# schematics.net
KiCad netlist of a schematic drawn in Altium Designer
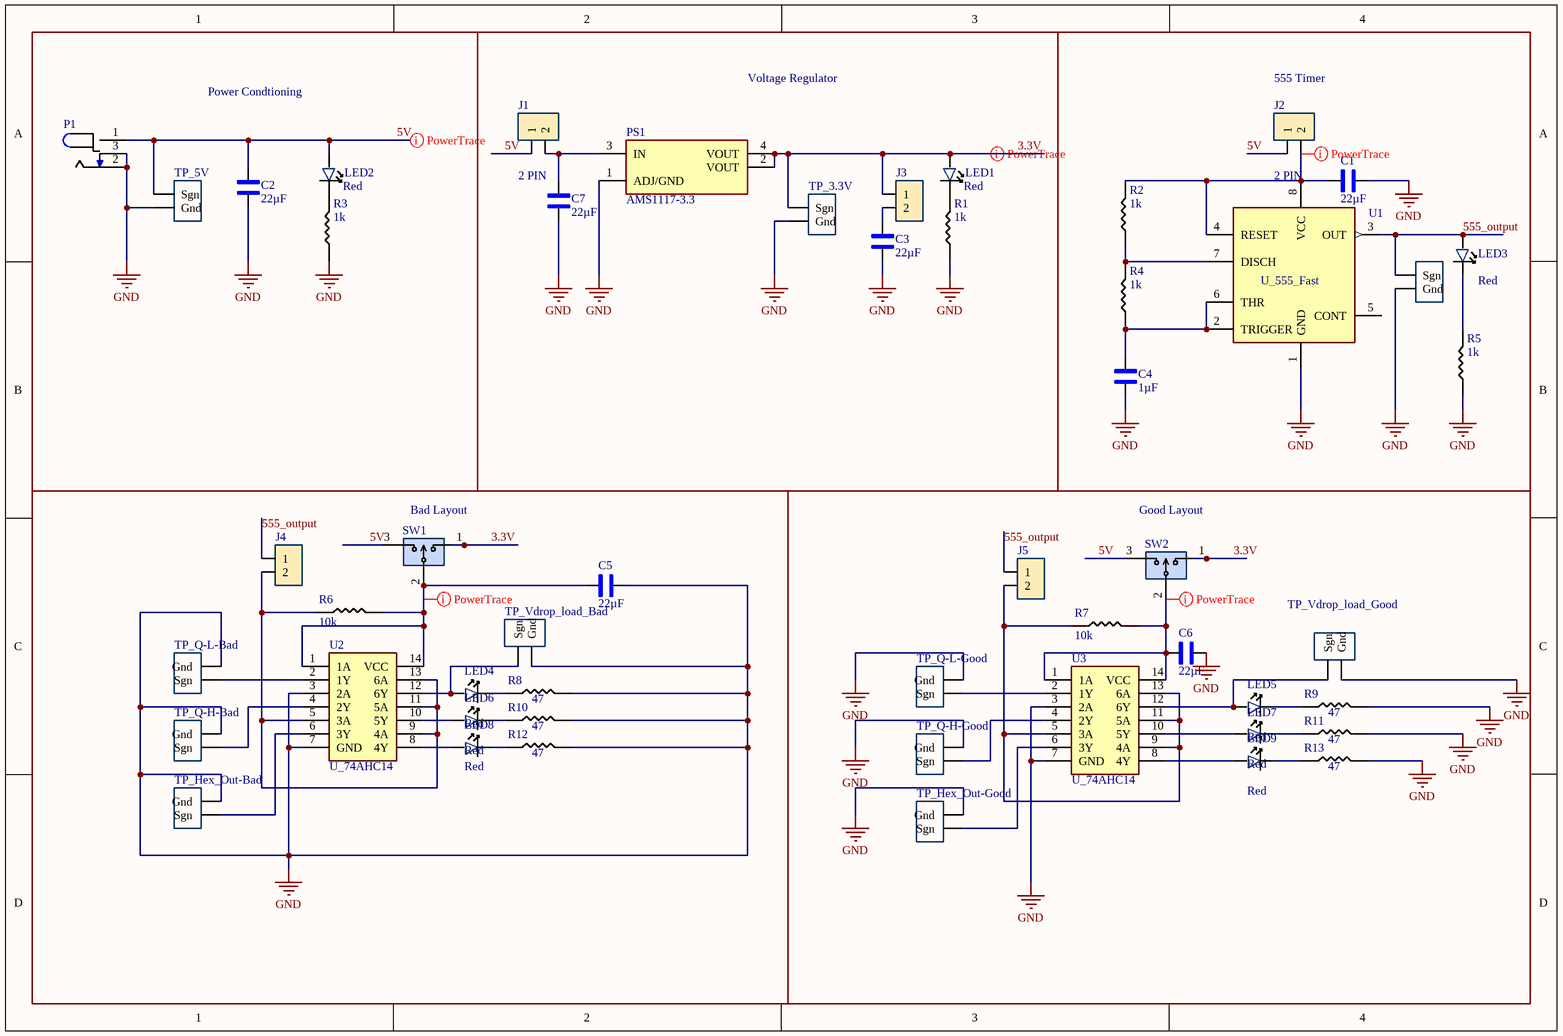
[diagram p0: schematics.SchDoc]

(export (version "E")
  (design (tool "Eeschema 10.0.6"))
  (components
    (comp (ref "C1")
      (value "22µF")
      (footprint "1206_Passive_Capacitor")
      (description "22uF ±10% 25V X5R 1206 Multilayer Ceramic Capacitors MLCC - SMD/SMT RoHS")
      (fields (field (name "LCSC PART#") "C12891") (field (name "MFR PART #") "CL31A226KAHNNNE"))
      (libsource (lib "University of Colorado") (part "C_47nF_1206"))
    )
    (comp (ref "C2")
      (value "22µF")
      (footprint "1206_Passive_Capacitor")
      (description "22uF ±10% 25V X5R 1206 Multilayer Ceramic Capacitors MLCC - SMD/SMT RoHS")
      (fields (field (name "LCSC PART#") "C12891") (field (name "MFR PART #") "CL31A226KAHNNNE"))
      (libsource (lib "University of Colorado") (part "C_47nF_1206"))
    )
    (comp (ref "C3")
      (value "22µF")
      (footprint "1206_Passive_Capacitor")
      (description "22uF ±10% 25V X5R 1206 Multilayer Ceramic Capacitors MLCC - SMD/SMT RoHS")
      (fields (field (name "LCSC PART#") "C12891") (field (name "MFR PART #") "CL31A226KAHNNNE"))
      (libsource (lib "University of Colorado") (part "C_47nF_1206"))
    )
    (comp (ref "C4")
      (value "1µF")
      (footprint "1206_Passive_Capacitor")
      (description "MULTILAYER CERAMIC CAPACITORS MLCC - SMD/SMT 1UF 50V 1206 ROHS")
      (fields (field (name "MFR PART #") "CL31B105KBHNNNE") (field (name "LCSC PART#") "C1848"))
      (libsource (lib "University of Colorado") (part "C_47nF_1206"))
    )
    (comp (ref "C5")
      (value "22µF")
      (footprint "1206_Passive_Capacitor")
      (description "22uF ±10% 25V X5R 1206 Multilayer Ceramic Capacitors MLCC - SMD/SMT RoHS")
      (fields (field (name "LCSC PART#") "C12891") (field (name "MFR PART #") "CL31A226KAHNNNE"))
      (libsource (lib "University of Colorado") (part "C_47nF_1206"))
    )
    (comp (ref "C6")
      (value "22µF")
      (footprint "1206_Passive_Capacitor")
      (description "22uF ±10% 25V X5R 1206 Multilayer Ceramic Capacitors MLCC - SMD/SMT RoHS")
      (fields (field (name "LCSC PART#") "C12891") (field (name "MFR PART #") "CL31A226KAHNNNE"))
      (libsource (lib "University of Colorado") (part "C_47nF_1206"))
    )
    (comp (ref "C7")
      (value "22µF")
      (footprint "1206_Passive_Capacitor")
      (description "22uF ±10% 25V X5R 1206 Multilayer Ceramic Capacitors MLCC - SMD/SMT RoHS")
      (fields (field (name "LCSC PART#") "C12891") (field (name "MFR PART #") "CL31A226KAHNNNE"))
      (libsource (lib "University of Colorado") (part "C_47nF_1206"))
    )
    (comp (ref "J1")
      (value "2 PIN")
      (footprint "2_PIN_100MIL")
      (description "2.54mm Straight 2 1 Header,Breakaway Through Hole,P=2.54mm Pin Header & Female Header ROHS")
      (fields (field (name "LCSC PART#") "C124375") (field (name "MFR PART #") "B-2100S02P-A110"))
      (libsource (lib "University of Colorado") (part "JM_2_PIN_MALE"))
    )
    (comp (ref "J2")
      (value "2 PIN")
      (footprint "2_PIN_100MIL")
      (description "2.54mm Straight 2 1 Header,Breakaway Through Hole,P=2.54mm Pin Header & Female Header ROHS")
      (fields (field (name "LCSC PART#") "C124375") (field (name "MFR PART #") "B-2100S02P-A110"))
      (libsource (lib "University of Colorado") (part "JM_2_PIN_MALE"))
    )
    (comp (ref "J3")
      (value "JM_2_PIN_MALE")
      (footprint "2_PIN_100MIL")
      (description "2.54mm Straight 2 1 Header,Breakaway Through Hole,P=2.54mm Pin Header & Female Header ROHS")
      (fields (field (name "LCSC PART#") "C124375") (field (name "MFR PART #") "B-2100S02P-A110"))
      (libsource (lib "") (part "JM_2_PIN_MALE_1"))
    )
    (comp (ref "J4")
      (value "JM_2_PIN_MALE")
      (footprint "2_PIN_100MIL")
      (description "2.54mm Straight 2 1 Header,Breakaway Through Hole,P=2.54mm Pin Header & Female Header ROHS")
      (fields (field (name "LCSC PART#") "C124375") (field (name "MFR PART #") "B-2100S02P-A110"))
      (libsource (lib "") (part "JM_2_PIN_MALE_1"))
    )
    (comp (ref "J5")
      (value "JM_2_PIN_MALE")
      (footprint "2_PIN_100MIL")
      (description "2.54mm Straight 2 1 Header,Breakaway Through Hole,P=2.54mm Pin Header & Female Header ROHS")
      (fields (field (name "LCSC PART#") "C124375") (field (name "MFR PART #") "B-2100S02P-A110"))
      (libsource (lib "") (part "JM_2_PIN_MALE_1"))
    )
    (comp (ref "LED1")
      (value "Red")
      (footprint "LED_1206")
      (description "Red 621~631nm 1206 Light Emitting Diodes (LED) RoHS")
      (fields (field (name "LCSC PART#") "C93133") (field (name "MFR PART #") "15-21/R6C-FQ1R1B/2T"))
      (libsource (lib "University of Colorado") (part "LED_YELLOW_1206"))
    )
    (comp (ref "LED2")
      (value "Red")
      (footprint "LED_1206")
      (description "Red 621~631nm 1206 Light Emitting Diodes (LED) RoHS")
      (fields (field (name "LCSC PART#") "C93133") (field (name "MFR PART #") "15-21/R6C-FQ1R1B/2T"))
      (libsource (lib "University of Colorado") (part "LED_YELLOW_1206"))
    )
    (comp (ref "LED3")
      (value "Red")
      (footprint "LED_1206")
      (description "Red 621~631nm 1206 Light Emitting Diodes (LED) RoHS")
      (fields (field (name "LCSC PART#") "C93133") (field (name "MFR PART #") "15-21/R6C-FQ1R1B/2T"))
      (libsource (lib "University of Colorado") (part "LED_YELLOW_1206"))
    )
    (comp (ref "LED4")
      (value "Red")
      (footprint "LED_1206")
      (description "Red 621~631nm 1206 Light Emitting Diodes (LED) RoHS")
      (fields (field (name "MFR PART #") "15-21/R6C-FQ1R1B/2T") (field (name "LCSC PART#") "C93133"))
      (libsource (lib "University of Colorado") (part "LED_YELLOW_1206"))
    )
    (comp (ref "LED5")
      (value "Red")
      (footprint "LED_1206")
      (description "Red 621~631nm 1206 Light Emitting Diodes (LED) RoHS")
      (fields (field (name "MFR PART #") "15-21/R6C-FQ1R1B/2T") (field (name "LCSC PART#") "C93133"))
      (libsource (lib "University of Colorado") (part "LED_YELLOW_1206"))
    )
    (comp (ref "LED6")
      (value "Red")
      (footprint "LED_1206")
      (description "Red 621~631nm 1206 Light Emitting Diodes (LED) RoHS")
      (fields (field (name "MFR PART #") "15-21/R6C-FQ1R1B/2T") (field (name "LCSC PART#") "C93133"))
      (libsource (lib "University of Colorado") (part "LED_YELLOW_1206"))
    )
    (comp (ref "LED7")
      (value "Red")
      (footprint "LED_1206")
      (description "Red 621~631nm 1206 Light Emitting Diodes (LED) RoHS")
      (fields (field (name "MFR PART #") "15-21/R6C-FQ1R1B/2T") (field (name "LCSC PART#") "C93133"))
      (libsource (lib "University of Colorado") (part "LED_YELLOW_1206"))
    )
    (comp (ref "LED8")
      (value "Red")
      (footprint "LED_1206")
      (description "Red 621~631nm 1206 Light Emitting Diodes (LED) RoHS")
      (fields (field (name "MFR PART #") "15-21/R6C-FQ1R1B/2T") (field (name "LCSC PART#") "C93133"))
      (libsource (lib "University of Colorado") (part "LED_YELLOW_1206"))
    )
    (comp (ref "LED9")
      (value "Red")
      (footprint "LED_1206")
      (description "Red 621~631nm 1206 Light Emitting Diodes (LED) RoHS")
      (fields (field (name "MFR PART #") "15-21/R6C-FQ1R1B/2T") (field (name "LCSC PART#") "C93133"))
      (libsource (lib "University of Colorado") (part "LED_YELLOW_1206"))
    )
    (comp (ref "P1")
      (value "P_Power Jack")
      (footprint "Power_Jack")
      (description "Power Barrel Connector Jack 2.10mm ID (0.083\"), 5.50mm OD (0.217\") Through Hole, Right Angle")
      (fields (field (name "LCSC PART#") "C136744") (field (name "MFR PART #") "PJ-102A"))
      (libsource (lib "University of Colorado") (part "P_Power Jack"))
    )
    (comp (ref "PS1")
      (value "PS_AMS_LDO_3v3")
      (footprint "LDO")
      (description "LOW DROPOUT REGULATORS(LDO) POSITIVE FIXED 1.3V @ 800MA 15V 3.3V 1A SOT-223 ROHS")
      (fields (field (name "MFR PART #") "AMS1117-3.3") (field (name "LCSC PART#") "C6186"))
      (libsource (lib "University of Colorado") (part "PS_AMS_LDO_3v3"))
    )
    (comp (ref "R1")
      (value "1k")
      (footprint "1206_Passive_Resitor")
      (description "CHIP RESISTOR - SURFACE MOUNT 1KOHMS ±1% 1/4W 1206 ROHS")
      (fields (field (name "LCSC PART#") "C4410") (field (name "MFR PART #") "RNCP1206FTD1K00CT"))
      (libsource (lib "University of Colorado") (part "R_500mOhm_1206"))
    )
    (comp (ref "R2")
      (value "1k")
      (footprint "1206_Passive_Resitor")
      (description "CHIP RESISTOR - SURFACE MOUNT 1KOHMS ±1% 1/4W 1206 ROHS")
      (fields (field (name "LCSC PART#") "C4410") (field (name "MFR PART #") "RNCP1206FTD1K00CT"))
      (libsource (lib "University of Colorado") (part "R_500mOhm_1206"))
    )
    (comp (ref "R3")
      (value "1k")
      (footprint "1206_Passive_Resitor")
      (description "CHIP RESISTOR - SURFACE MOUNT 1KOHMS ±1% 1/4W 1206 ROHS")
      (fields (field (name "LCSC PART#") "C4410") (field (name "MFR PART #") "RNCP1206FTD1K00CT"))
      (libsource (lib "University of Colorado") (part "R_500mOhm_1206"))
    )
    (comp (ref "R4")
      (value "1k")
      (footprint "1206_Passive_Resitor")
      (description "CHIP RESISTOR - SURFACE MOUNT 1KOHMS ±1% 1/4W 1206 ROHS")
      (fields (field (name "LCSC PART#") "C4410") (field (name "MFR PART #") "RNCP1206FTD1K00CT"))
      (libsource (lib "University of Colorado") (part "R_500mOhm_1206"))
    )
    (comp (ref "R5")
      (value "1k")
      (footprint "1206_Passive_Resitor")
      (description "CHIP RESISTOR - SURFACE MOUNT 1KOHMS ±1% 1/4W 1206 ROHS")
      (fields (field (name "LCSC PART#") "C4410") (field (name "MFR PART #") "RNCP1206FTD1K00CT"))
      (libsource (lib "University of Colorado") (part "R_500mOhm_1206"))
    )
    (comp (ref "R6")
      (value "10k")
      (footprint "1206_Passive_Resitor")
      (description "10 kOhms ±5% 0.25W, 1/4W Chip Resistor 1206 (3216 Metric) Automotive AEC-Q200 Thick Film")
      (fields (field (name "MFR PART #") "RMCF1206FT10K0") (field (name "LCSC PART#") "C17902"))
      (libsource (lib "University of Colorado") (part "R_500mOhm_1206"))
    )
    (comp (ref "R7")
      (value "10k")
      (footprint "1206_Passive_Resitor")
      (description "10 kOhms ±5% 0.25W, 1/4W Chip Resistor 1206 (3216 Metric) Automotive AEC-Q200 Thick Film")
      (fields (field (name "MFR PART #") "RMCF1206FT10K0") (field (name "LCSC PART#") "C17902"))
      (libsource (lib "University of Colorado") (part "R_500mOhm_1206"))
    )
    (comp (ref "R8")
      (value "47")
      (footprint "1206_Passive_Resitor")
      (description "47O ±5% 0.25W ±200ppm/? 1206 Chip Resistor - Surface Mount RoHS")
      (fields (field (name "MFR PART #") "1206W4J0470T5E") (field (name "LCSC PART#") "C25384"))
      (libsource (lib "University of Colorado") (part "R_500mOhm_1206"))
    )
    (comp (ref "R9")
      (value "47")
      (footprint "1206_Passive_Resitor")
      (description "47O ±5% 0.25W ±200ppm/? 1206 Chip Resistor - Surface Mount RoHS")
      (fields (field (name "MFR PART #") "1206W4J0470T5E") (field (name "LCSC PART#") "C25384"))
      (libsource (lib "University of Colorado") (part "R_500mOhm_1206"))
    )
    (comp (ref "R10")
      (value "47")
      (footprint "1206_Passive_Resitor")
      (description "47O ±5% 0.25W ±200ppm/? 1206 Chip Resistor - Surface Mount RoHS")
      (fields (field (name "MFR PART #") "1206W4J0470T5E") (field (name "LCSC PART#") "C25384"))
      (libsource (lib "University of Colorado") (part "R_500mOhm_1206"))
    )
    (comp (ref "R11")
      (value "47")
      (footprint "1206_Passive_Resitor")
      (description "47O ±5% 0.25W ±200ppm/? 1206 Chip Resistor - Surface Mount RoHS")
      (fields (field (name "MFR PART #") "1206W4J0470T5E") (field (name "LCSC PART#") "C25384"))
      (libsource (lib "University of Colorado") (part "R_500mOhm_1206"))
    )
    (comp (ref "R12")
      (value "47")
      (footprint "1206_Passive_Resitor")
      (description "47O ±5% 0.25W ±200ppm/? 1206 Chip Resistor - Surface Mount RoHS")
      (fields (field (name "MFR PART #") "1206W4J0470T5E") (field (name "LCSC PART#") "C25384"))
      (libsource (lib "University of Colorado") (part "R_500mOhm_1206"))
    )
    (comp (ref "R13")
      (value "47")
      (footprint "1206_Passive_Resitor")
      (description "47O ±5% 0.25W ±200ppm/? 1206 Chip Resistor - Surface Mount RoHS")
      (fields (field (name "MFR PART #") "1206W4J0470T5E") (field (name "LCSC PART#") "C25384"))
      (libsource (lib "University of Colorado") (part "R_500mOhm_1206"))
    )
    (comp (ref "SW1")
      (value "SW_3Pin_100mil_Switch")
      (footprint "3_PIN_100mil")
      (description "Connector Header Through Hole 3 position 0.100\" (2.54mm)")
      (fields (field (name "LCSC PART#") "C49257") (field (name "MFR PART #") "PREC003SAAN-RC"))
      (libsource (lib "University of Colorado") (part "SW_3Pin_100mil_Switch"))
    )
    (comp (ref "SW2")
      (value "SW_3Pin_100mil_Switch")
      (footprint "3_PIN_100mil")
      (description "Connector Header Through Hole 3 position 0.100\" (2.54mm)")
      (fields (field (name "LCSC PART#") "C49257") (field (name "MFR PART #") "PREC003SAAN-RC"))
      (libsource (lib "University of Colorado") (part "SW_3Pin_100mil_Switch"))
    )
    (comp (ref "TP_3.3V")
      (value "TP_10x_Probe")
      (footprint "TP10x_Probe")
      (description "Test Point 300 mil centers")
      (libsource (lib "University of Colorado") (part "TP_10x_Probe"))
    )
    (comp (ref "TP_5V")
      (value "TP_10x_Probe")
      (footprint "TP10x_Probe")
      (description "Test Point 300 mil centers")
      (libsource (lib "University of Colorado") (part "TP_10x_Probe"))
    )
    (comp (ref "TP_555_output")
      (value "TP_10x_Probe")
      (footprint "TP10x_Probe")
      (description "Test Point 300 mil centers")
      (libsource (lib "University of Colorado") (part "TP_10x_Probe"))
    )
    (comp (ref "TP_Hex_Out-Bad")
      (value "TP_10x_Probe")
      (footprint "TP10x_Probe")
      (description "Test Point 300 mil centers")
      (libsource (lib "") (part "TP_10x_Probe_1"))
    )
    (comp (ref "TP_Hex_Out-Good")
      (value "TP_10x_Probe")
      (footprint "TP10x_Probe")
      (description "Test Point 300 mil centers")
      (libsource (lib "") (part "TP_10x_Probe_1"))
    )
    (comp (ref "TP_Q-H-Bad")
      (value "TP_10x_Probe")
      (footprint "TP10x_Probe")
      (description "Test Point 300 mil centers")
      (libsource (lib "") (part "TP_10x_Probe_1"))
    )
    (comp (ref "TP_Q-H-Good")
      (value "TP_10x_Probe")
      (footprint "TP10x_Probe")
      (description "Test Point 300 mil centers")
      (libsource (lib "") (part "TP_10x_Probe_1"))
    )
    (comp (ref "TP_Q-L-Bad")
      (value "TP_10x_Probe")
      (footprint "TP10x_Probe")
      (description "Test Point 300 mil centers")
      (libsource (lib "") (part "TP_10x_Probe_1"))
    )
    (comp (ref "TP_Q-L-Good")
      (value "TP_10x_Probe")
      (footprint "TP10x_Probe")
      (description "Test Point 300 mil centers")
      (libsource (lib "") (part "TP_10x_Probe_1"))
    )
    (comp (ref "TP_Vdrop_load_Bad")
      (value "TP_10x_Probe")
      (footprint "TP10x_Probe")
      (description "Test Point 300 mil centers")
      (libsource (lib "") (part "TP_10x_Probe_2"))
    )
    (comp (ref "TP_Vdrop_load_Good")
      (value "TP_10x_Probe")
      (footprint "TP10x_Probe")
      (description "Test Point 300 mil centers")
      (libsource (lib "") (part "TP_10x_Probe_2"))
    )
    (comp (ref "U1")
      (value "U_555_Fast")
      (footprint "TS555IDTTR")
      (description "555 Type, Timer/Oscillator _Single_ IC 3MHz 8-SO")
      (fields (field (name "LCSC PART#") "C90760") (field (name "MFR PART #") "LMC555CMX/NOPB"))
      (libsource (lib "University of Colorado") (part "U_555_Slow"))
    )
    (comp (ref "U2")
      (value "U_74AHC14")
      (footprint "HEX_74AC14")
      (description "Inverter IC 6 Channel Schmitt Trigger 14-SOIC")
      (fields (field (name "MFR PART #") "SN74AHC14DR") (field (name "LCSC PART#") "C6942"))
      (libsource (lib "University of Colorado") (part "U_7414HC14"))
    )
    (comp (ref "U3")
      (value "U_74AHC14")
      (footprint "HEX_74AC14")
      (description "Inverter IC 6 Channel Schmitt Trigger 14-SOIC")
      (fields (field (name "MFR PART #") "SN74AHC14DR") (field (name "LCSC PART#") "C6942"))
      (libsource (lib "University of Colorado") (part "U_7414HC14"))
    )
  )
  (nets
    (net (code "1") (name "/3.3V") (class "Default")
      (node (ref "J3") (pin "1") (pinfunction "1_1") (pintype "passive"))
      (node (ref "LED1") (pin "1") (pinfunction "1_1") (pintype "passive"))
      (node (ref "PS1") (pin "2") (pinfunction "VOUT_2") (pintype "power_in"))
      (node (ref "PS1") (pin "4") (pinfunction "VOUT_4") (pintype "power_in"))
      (node (ref "SW1") (pin "1") (pinfunction "1_1") (pintype "passive"))
      (node (ref "SW2") (pin "1") (pinfunction "1_1") (pintype "passive"))
      (node (ref "TP_3.3V") (pin "1") (pinfunction "Sgn_1") (pintype "passive"))
    )
    (net (code "2") (name "/5V") (class "Default")
      (node (ref "C2") (pin "2") (pinfunction "2_2") (pintype "passive"))
      (node (ref "J1") (pin "1") (pinfunction "1_1") (pintype "passive"))
      (node (ref "J2") (pin "1") (pinfunction "1_1") (pintype "passive"))
      (node (ref "LED2") (pin "1") (pinfunction "1_1") (pintype "passive"))
      (node (ref "P1") (pin "1") (pinfunction "1_1") (pintype "power_in"))
      (node (ref "SW1") (pin "3") (pinfunction "3_3") (pintype "passive"))
      (node (ref "SW2") (pin "3") (pinfunction "3_3") (pintype "passive"))
      (node (ref "TP_5V") (pin "1") (pinfunction "Sgn_1") (pintype "passive"))
    )
    (net (code "3") (name "/555_output") (class "Default")
      (node (ref "J4") (pin "1") (pinfunction "1_1") (pintype "passive"))
      (node (ref "J5") (pin "1") (pinfunction "1_1") (pintype "passive"))
      (node (ref "LED3") (pin "1") (pinfunction "1_1") (pintype "passive"))
      (node (ref "TP_555_output") (pin "1") (pinfunction "Sgn_1") (pintype "passive"))
      (node (ref "U1") (pin "3") (pinfunction "OUT_3") (pintype "output"))
    )
    (net (code "4") (name "GND") (class "Default")
      (node (ref "C1") (pin "2") (pinfunction "2_2") (pintype "passive"))
      (node (ref "C2") (pin "1") (pinfunction "1_1") (pintype "passive"))
      (node (ref "C3") (pin "2") (pinfunction "2_2") (pintype "passive"))
      (node (ref "C4") (pin "1") (pinfunction "1_1") (pintype "passive"))
      (node (ref "C5") (pin "1") (pinfunction "1_1") (pintype "passive"))
      (node (ref "C6") (pin "1") (pinfunction "1_1") (pintype "passive"))
      (node (ref "C7") (pin "2") (pinfunction "2_2") (pintype "passive"))
      (node (ref "P1") (pin "2") (pinfunction "2_2") (pintype "power_in"))
      (node (ref "P1") (pin "3") (pinfunction "3_3") (pintype "power_in"))
      (node (ref "PS1") (pin "1") (pinfunction "ADJ/GND_1") (pintype "passive"))
      (node (ref "R1") (pin "1") (pinfunction "1_1") (pintype "passive"))
      (node (ref "R10") (pin "2") (pinfunction "2_2") (pintype "passive"))
      (node (ref "R11") (pin "2") (pinfunction "2_2") (pintype "passive"))
      (node (ref "R12") (pin "2") (pinfunction "2_2") (pintype "passive"))
      (node (ref "R13") (pin "2") (pinfunction "2_2") (pintype "passive"))
      (node (ref "R3") (pin "1") (pinfunction "1_1") (pintype "passive"))
      (node (ref "R5") (pin "1") (pinfunction "1_1") (pintype "passive"))
      (node (ref "R8") (pin "2") (pinfunction "2_2") (pintype "passive"))
      (node (ref "R9") (pin "2") (pinfunction "2_2") (pintype "passive"))
      (node (ref "TP_3.3V") (pin "2") (pinfunction "Gnd_2") (pintype "passive"))
      (node (ref "TP_555_output") (pin "2") (pinfunction "Gnd_2") (pintype "passive"))
      (node (ref "TP_5V") (pin "2") (pinfunction "Gnd_2") (pintype "passive"))
      (node (ref "TP_Hex_Out-Bad") (pin "2") (pinfunction "Gnd_2") (pintype "passive"))
      (node (ref "TP_Hex_Out-Good") (pin "2") (pinfunction "Gnd_2") (pintype "passive"))
      (node (ref "TP_Q-H-Bad") (pin "2") (pinfunction "Gnd_2") (pintype "passive"))
      (node (ref "TP_Q-H-Good") (pin "2") (pinfunction "Gnd_2") (pintype "passive"))
      (node (ref "TP_Q-L-Bad") (pin "2") (pinfunction "Gnd_2") (pintype "passive"))
      (node (ref "TP_Q-L-Good") (pin "2") (pinfunction "Gnd_2") (pintype "passive"))
      (node (ref "TP_Vdrop_load_Bad") (pin "2") (pinfunction "Gnd_2") (pintype "passive"))
      (node (ref "TP_Vdrop_load_Good") (pin "2") (pinfunction "Gnd_2") (pintype "passive"))
      (node (ref "U1") (pin "1") (pinfunction "GND_1") (pintype "power_in"))
      (node (ref "U2") (pin "3") (pinfunction "2A_3") (pintype "passive"))
      (node (ref "U2") (pin "7") (pinfunction "GND_7") (pintype "passive"))
      (node (ref "U3") (pin "3") (pinfunction "2A_3") (pintype "passive"))
      (node (ref "U3") (pin "7") (pinfunction "GND_7") (pintype "passive"))
    )
    (net (code "5") (name "Net-(C3-Pad1)") (class "Default")
      (node (ref "C3") (pin "1") (pinfunction "1_1") (pintype "passive"))
      (node (ref "J3") (pin "2") (pinfunction "2_2") (pintype "passive"))
    )
    (net (code "6") (name "Net-(LED1-Pad2)") (class "Default")
      (node (ref "LED1") (pin "2") (pinfunction "2_2") (pintype "passive"))
      (node (ref "R1") (pin "2") (pinfunction "2_2") (pintype "passive"))
    )
    (net (code "7") (name "Net-(LED2-Pad2)") (class "Default")
      (node (ref "LED2") (pin "2") (pinfunction "2_2") (pintype "passive"))
      (node (ref "R3") (pin "2") (pinfunction "2_2") (pintype "passive"))
    )
    (net (code "8") (name "Net-(LED3-Pad2)") (class "Default")
      (node (ref "LED3") (pin "2") (pinfunction "2_2") (pintype "passive"))
      (node (ref "R5") (pin "2") (pinfunction "2_2") (pintype "passive"))
    )
    (net (code "9") (name "Net-(LED4-Pad2)") (class "Default")
      (node (ref "LED4") (pin "2") (pinfunction "2_2") (pintype "passive"))
      (node (ref "R8") (pin "1") (pinfunction "1_1") (pintype "passive"))
    )
    (net (code "10") (name "Net-(LED5-Pad2)") (class "Default")
      (node (ref "LED5") (pin "2") (pinfunction "2_2") (pintype "passive"))
      (node (ref "R9") (pin "1") (pinfunction "1_1") (pintype "passive"))
    )
    (net (code "11") (name "Net-(LED6-Pad2)") (class "Default")
      (node (ref "LED6") (pin "2") (pinfunction "2_2") (pintype "passive"))
      (node (ref "R10") (pin "1") (pinfunction "1_1") (pintype "passive"))
    )
    (net (code "12") (name "Net-(LED7-Pad2)") (class "Default")
      (node (ref "LED7") (pin "2") (pinfunction "2_2") (pintype "passive"))
      (node (ref "R11") (pin "1") (pinfunction "1_1") (pintype "passive"))
    )
    (net (code "13") (name "Net-(LED8-Pad2)") (class "Default")
      (node (ref "LED8") (pin "2") (pinfunction "2_2") (pintype "passive"))
      (node (ref "R12") (pin "1") (pinfunction "1_1") (pintype "passive"))
    )
    (net (code "14") (name "Net-(LED9-Pad2)") (class "Default")
      (node (ref "LED9") (pin "2") (pinfunction "2_2") (pintype "passive"))
      (node (ref "R13") (pin "1") (pinfunction "1_1") (pintype "passive"))
    )
    (net (code "15") (name "Net-(PS1-IN)") (class "Default")
      (node (ref "C7") (pin "1") (pinfunction "1_1") (pintype "passive"))
      (node (ref "J1") (pin "2") (pinfunction "2_2") (pintype "passive"))
      (node (ref "PS1") (pin "3") (pinfunction "IN_3") (pintype "power_in"))
    )
    (net (code "16") (name "Net-(TP_Hex_Out-Bad-Sgn)") (class "Default")
      (node (ref "TP_Hex_Out-Bad") (pin "1") (pinfunction "Sgn_1") (pintype "passive"))
      (node (ref "U2") (pin "6") (pinfunction "3Y_6") (pintype "passive"))
    )
    (net (code "17") (name "Net-(TP_Hex_Out-Good-Sgn)") (class "Default")
      (node (ref "TP_Hex_Out-Good") (pin "1") (pinfunction "Sgn_1") (pintype "passive"))
      (node (ref "U3") (pin "6") (pinfunction "3Y_6") (pintype "passive"))
    )
    (net (code "18") (name "Net-(TP_Q-H-Bad-Sgn)") (class "Default")
      (node (ref "TP_Q-H-Bad") (pin "1") (pinfunction "Sgn_1") (pintype "passive"))
      (node (ref "U2") (pin "4") (pinfunction "2Y_4") (pintype "passive"))
    )
    (net (code "19") (name "Net-(TP_Q-H-Good-Sgn)") (class "Default")
      (node (ref "TP_Q-H-Good") (pin "1") (pinfunction "Sgn_1") (pintype "passive"))
      (node (ref "U3") (pin "4") (pinfunction "2Y_4") (pintype "passive"))
    )
    (net (code "20") (name "Net-(TP_Q-L-Bad-Sgn)") (class "Default")
      (node (ref "TP_Q-L-Bad") (pin "1") (pinfunction "Sgn_1") (pintype "passive"))
      (node (ref "U2") (pin "2") (pinfunction "1Y_2") (pintype "passive"))
    )
    (net (code "21") (name "Net-(TP_Q-L-Good-Sgn)") (class "Default")
      (node (ref "TP_Q-L-Good") (pin "1") (pinfunction "Sgn_1") (pintype "passive"))
      (node (ref "U3") (pin "2") (pinfunction "1Y_2") (pintype "passive"))
    )
    (net (code "22") (name "Net-(TP_Vdrop_load_Bad-Sgn)") (class "Default")
      (node (ref "LED4") (pin "1") (pinfunction "1_1") (pintype "passive"))
      (node (ref "TP_Vdrop_load_Bad") (pin "1") (pinfunction "Sgn_1") (pintype "passive"))
      (node (ref "U2") (pin "12") (pinfunction "6Y_12") (pintype "passive"))
    )
    (net (code "23") (name "Net-(TP_Vdrop_load_Good-Sgn)") (class "Default")
      (node (ref "LED5") (pin "1") (pinfunction "1_1") (pintype "passive"))
      (node (ref "TP_Vdrop_load_Good") (pin "1") (pinfunction "Sgn_1") (pintype "passive"))
      (node (ref "U3") (pin "12") (pinfunction "6Y_12") (pintype "passive"))
    )
    (net (code "24") (name "Net-(U1-DISCH)") (class "Default")
      (node (ref "R2") (pin "1") (pinfunction "1_1") (pintype "passive"))
      (node (ref "R4") (pin "2") (pinfunction "2_2") (pintype "passive"))
      (node (ref "U1") (pin "7") (pinfunction "DISCH_7") (pintype "passive"))
    )
    (net (code "25") (name "Net-(U1-RESET)") (class "Default")
      (node (ref "C1") (pin "1") (pinfunction "1_1") (pintype "passive"))
      (node (ref "J2") (pin "2") (pinfunction "2_2") (pintype "passive"))
      (node (ref "R2") (pin "2") (pinfunction "2_2") (pintype "passive"))
      (node (ref "U1") (pin "4") (pinfunction "RESET_4") (pintype "passive"))
      (node (ref "U1") (pin "8") (pinfunction "VCC_8") (pintype "power_in"))
    )
    (net (code "26") (name "Net-(U1-THR)") (class "Default")
      (node (ref "C4") (pin "2") (pinfunction "2_2") (pintype "passive"))
      (node (ref "R4") (pin "1") (pinfunction "1_1") (pintype "passive"))
      (node (ref "U1") (pin "2") (pinfunction "TRIGGER_2") (pintype "passive"))
      (node (ref "U1") (pin "6") (pinfunction "THR_6") (pintype "passive"))
    )
    (net (code "27") (name "Net-(U2-1A)") (class "Default")
      (node (ref "C5") (pin "2") (pinfunction "2_2") (pintype "passive"))
      (node (ref "R6") (pin "2") (pinfunction "2_2") (pintype "passive"))
      (node (ref "SW1") (pin "2") (pinfunction "2_2") (pintype "passive"))
      (node (ref "U2") (pin "1") (pinfunction "1A_1") (pintype "passive"))
      (node (ref "U2") (pin "14") (pinfunction "VCC_14") (pintype "passive"))
    )
    (net (code "28") (name "Net-(U2-3A)") (class "Default")
      (node (ref "J4") (pin "2") (pinfunction "2_2") (pintype "passive"))
      (node (ref "R6") (pin "1") (pinfunction "1_1") (pintype "passive"))
      (node (ref "U2") (pin "11") (pinfunction "5A_11") (pintype "passive"))
      (node (ref "U2") (pin "13") (pinfunction "6A_13") (pintype "passive"))
      (node (ref "U2") (pin "5") (pinfunction "3A_5") (pintype "passive"))
      (node (ref "U2") (pin "9") (pinfunction "4A_9") (pintype "passive"))
    )
    (net (code "29") (name "Net-(U2-4Y)") (class "Default")
      (node (ref "LED8") (pin "1") (pinfunction "1_1") (pintype "passive"))
      (node (ref "U2") (pin "8") (pinfunction "4Y_8") (pintype "passive"))
    )
    (net (code "30") (name "Net-(U2-5Y)") (class "Default")
      (node (ref "LED6") (pin "1") (pinfunction "1_1") (pintype "passive"))
      (node (ref "U2") (pin "10") (pinfunction "5Y_10") (pintype "passive"))
    )
    (net (code "31") (name "Net-(U3-1A)") (class "Default")
      (node (ref "C6") (pin "2") (pinfunction "2_2") (pintype "passive"))
      (node (ref "R7") (pin "2") (pinfunction "2_2") (pintype "passive"))
      (node (ref "SW2") (pin "2") (pinfunction "2_2") (pintype "passive"))
      (node (ref "U3") (pin "1") (pinfunction "1A_1") (pintype "passive"))
      (node (ref "U3") (pin "14") (pinfunction "VCC_14") (pintype "passive"))
    )
    (net (code "32") (name "Net-(U3-3A)") (class "Default")
      (node (ref "J5") (pin "2") (pinfunction "2_2") (pintype "passive"))
      (node (ref "R7") (pin "1") (pinfunction "1_1") (pintype "passive"))
      (node (ref "U3") (pin "11") (pinfunction "5A_11") (pintype "passive"))
      (node (ref "U3") (pin "13") (pinfunction "6A_13") (pintype "passive"))
      (node (ref "U3") (pin "5") (pinfunction "3A_5") (pintype "passive"))
      (node (ref "U3") (pin "9") (pinfunction "4A_9") (pintype "passive"))
    )
    (net (code "33") (name "Net-(U3-4Y)") (class "Default")
      (node (ref "LED9") (pin "1") (pinfunction "1_1") (pintype "passive"))
      (node (ref "U3") (pin "8") (pinfunction "4Y_8") (pintype "passive"))
    )
    (net (code "34") (name "Net-(U3-5Y)") (class "Default")
      (node (ref "LED7") (pin "1") (pinfunction "1_1") (pintype "passive"))
      (node (ref "U3") (pin "10") (pinfunction "5Y_10") (pintype "passive"))
    )
    (net (code "35") (name "unconnected-(U1-CONT-Pad5)") (class "Default")
      (node (ref "U1") (pin "5") (pinfunction "CONT_5") (pintype "passive"))
    )
  )
)
